# Oscar_s_second_Schematic.net
KiCad netlist of a schematic drawn in EAGLE
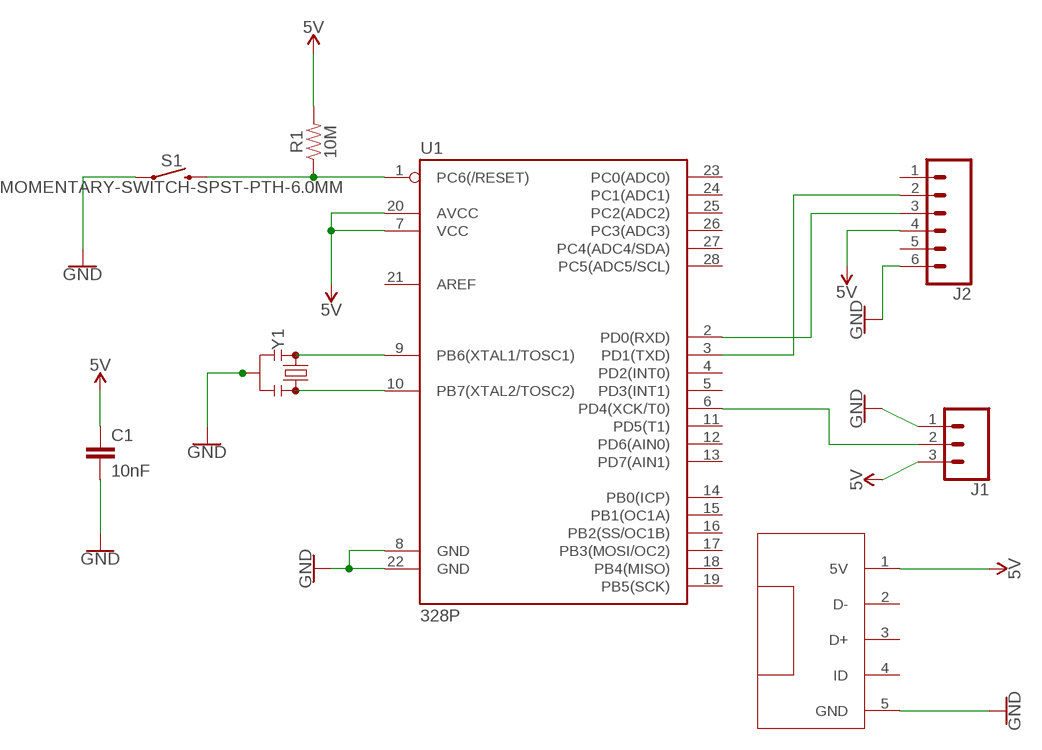
[diagram p0: schematic, sheet 1]

(export (version "E")
  (design (tool "Eeschema 10.0.6"))
  (components
    (comp (ref "C1")
      (value "10nF")
      (footprint "eagle-import:CAP-PTH-10MM")
      (libsource (lib "eagle-import") (part "10NF-PTH-10MM-10000V-1-%"))
    )
    (comp (ref "J1")
      (value "CONN_03")
      (footprint "eagle-import:1X03")
      (libsource (lib "eagle-import") (part "CONN_03"))
    )
    (comp (ref "J2")
      (value "CONN_06SILK_FEMALE_PTH")
      (footprint "eagle-import:1X06")
      (libsource (lib "eagle-import") (part "CONN_06SILK_FEMALE_PTH"))
    )
    (comp (ref "R1")
      (value "10M")
      (footprint "eagle-import:AXIAL-0.3")
      (libsource (lib "eagle-import") (part "10MOHM-HORIZ-1/4W-5%"))
    )
    (comp (ref "S1")
      (value "MOMENTARY-SWITCH-SPST-PTH-6.0MM")
      (footprint "eagle-import:TACTILE_SWITCH_PTH_6.0MM")
      (libsource (lib "eagle-import") (part "MOMENTARY-SWITCH-SPST-PTH-6.0MM"))
    )
    (comp (ref "U$1")
      (value "USB")
      (footprint "eagle-import:USB")
      (libsource (lib "eagle-import") (part "USB"))
    )
    (comp (ref "U1")
      (value "328P")
      (footprint "eagle-import:DIP28")
      (libsource (lib "eagle-import") (part "ATMEGA328P_PDIP"))
    )
    (comp (ref "Y1")
      (value "RESONATORPTH-7.6X3.8")
      (footprint "eagle-import:RESONATOR-PTH-7.6X3.8")
      (libsource (lib "eagle-import") (part "RESONATORPTH-7.6X3.8"))
    )
  )
  (nets
    (net (code "1") (name "5V") (class "Default")
      (node (ref "C1") (pin "1") (pinfunction "1_1") (pintype "passive"))
      (node (ref "J1") (pin "3") (pinfunction "3_3") (pintype "passive"))
      (node (ref "J2") (pin "4") (pinfunction "4_4") (pintype "passive"))
      (node (ref "R1") (pin "P$2") (pinfunction "2_P$2") (pintype "passive"))
      (node (ref "U$1") (pin "1") (pinfunction "5V_1") (pintype "bidirectional"))
      (node (ref "U1") (pin "20") (pinfunction "AVCC_20") (pintype "bidirectional"))
      (node (ref "U1") (pin "7") (pinfunction "VCC_7") (pintype "bidirectional"))
    )
    (net (code "2") (name "GND") (class "Default")
      (node (ref "C1") (pin "2") (pinfunction "2_2") (pintype "passive"))
      (node (ref "J1") (pin "1") (pinfunction "1_1") (pintype "passive"))
      (node (ref "J2") (pin "6") (pinfunction "6_6") (pintype "passive"))
      (node (ref "S1") (pin "1") (pinfunction "1_1") (pintype "passive"))
      (node (ref "U$1") (pin "5") (pinfunction "GND_5") (pintype "bidirectional"))
      (node (ref "U1") (pin "22") (pinfunction "GND_22") (pintype "bidirectional"))
      (node (ref "U1") (pin "8") (pinfunction "GND_8") (pintype "bidirectional"))
      (node (ref "Y1") (pin "2") (pinfunction "2_2") (pintype "passive"))
    )
    (net (code "3") (name "Net-(R1-1)") (class "Default")
      (node (ref "R1") (pin "P$1") (pinfunction "1_P$1") (pintype "passive"))
      (node (ref "S1") (pin "3") (pinfunction "2_3") (pintype "passive"))
      (node (ref "U1") (pin "1") (pinfunction "PC6(/RESET)_1") (pintype "bidirectional"))
    )
    (net (code "4") (name "Net-(U1-PB6(XTAL1{slash}TOSC1))") (class "Default")
      (node (ref "U1") (pin "9") (pinfunction "PB6(XTAL1/TOSC1)_9") (pintype "bidirectional"))
      (node (ref "Y1") (pin "1") (pinfunction "1_1") (pintype "passive"))
    )
    (net (code "5") (name "Net-(U1-PB7(XTAL2{slash}TOSC2))") (class "Default")
      (node (ref "U1") (pin "10") (pinfunction "PB7(XTAL2/TOSC2)_10") (pintype "bidirectional"))
      (node (ref "Y1") (pin "3") (pinfunction "3_3") (pintype "passive"))
    )
    (net (code "6") (name "Net-(U1-PD0(RXD))") (class "Default")
      (node (ref "J2") (pin "3") (pinfunction "3_3") (pintype "passive"))
      (node (ref "U1") (pin "2") (pinfunction "PD0(RXD)_2") (pintype "bidirectional"))
    )
    (net (code "7") (name "Net-(U1-PD1(TXD))") (class "Default")
      (node (ref "J2") (pin "2") (pinfunction "2_2") (pintype "passive"))
      (node (ref "U1") (pin "3") (pinfunction "PD1(TXD)_3") (pintype "bidirectional"))
    )
    (net (code "8") (name "Net-(U1-PD4(XCK{slash}T0))") (class "Default")
      (node (ref "J1") (pin "2") (pinfunction "2_2") (pintype "passive"))
      (node (ref "U1") (pin "6") (pinfunction "PD4(XCK/T0)_6") (pintype "bidirectional"))
    )
    (net (code "9") (name "unconnected-(J2-Pad1)") (class "Default")
      (node (ref "J2") (pin "1") (pinfunction "1_1") (pintype "passive"))
    )
    (net (code "10") (name "unconnected-(J2-Pad5)") (class "Default")
      (node (ref "J2") (pin "5") (pinfunction "5_5") (pintype "passive"))
    )
    (net (code "11") (name "unconnected-(U$1-D+-Pad3)") (class "Default")
      (node (ref "U$1") (pin "3") (pinfunction "D+_3") (pintype "bidirectional"))
    )
    (net (code "12") (name "unconnected-(U$1-D--Pad2)") (class "Default")
      (node (ref "U$1") (pin "2") (pinfunction "D-_2") (pintype "bidirectional"))
    )
    (net (code "13") (name "unconnected-(U$1-ID-Pad4)") (class "Default")
      (node (ref "U$1") (pin "4") (pinfunction "ID_4") (pintype "bidirectional"))
    )
    (net (code "14") (name "unconnected-(U1-AREF-Pad21)") (class "Default")
      (node (ref "U1") (pin "21") (pinfunction "AREF_21") (pintype "bidirectional"))
    )
    (net (code "15") (name "unconnected-(U1-PB0(ICP)-Pad14)") (class "Default")
      (node (ref "U1") (pin "14") (pinfunction "PB0(ICP)_14") (pintype "bidirectional"))
    )
    (net (code "16") (name "unconnected-(U1-PB1(OC1A)-Pad15)") (class "Default")
      (node (ref "U1") (pin "15") (pinfunction "PB1(OC1A)_15") (pintype "bidirectional"))
    )
    (net (code "17") (name "unconnected-(U1-PB2(SS{slash}OC1B)-Pad16)") (class "Default")
      (node (ref "U1") (pin "16") (pinfunction "PB2(SS/OC1B)_16") (pintype "bidirectional"))
    )
    (net (code "18") (name "unconnected-(U1-PB3(MOSI{slash}OC2)-Pad17)") (class "Default")
      (node (ref "U1") (pin "17") (pinfunction "PB3(MOSI/OC2)_17") (pintype "bidirectional"))
    )
    (net (code "19") (name "unconnected-(U1-PB4(MISO)-Pad18)") (class "Default")
      (node (ref "U1") (pin "18") (pinfunction "PB4(MISO)_18") (pintype "bidirectional"))
    )
    (net (code "20") (name "unconnected-(U1-PB5(SCK)-Pad19)") (class "Default")
      (node (ref "U1") (pin "19") (pinfunction "PB5(SCK)_19") (pintype "bidirectional"))
    )
    (net (code "21") (name "unconnected-(U1-PC0(ADC0)-Pad23)") (class "Default")
      (node (ref "U1") (pin "23") (pinfunction "PC0(ADC0)_23") (pintype "bidirectional"))
    )
    (net (code "22") (name "unconnected-(U1-PC1(ADC1)-Pad24)") (class "Default")
      (node (ref "U1") (pin "24") (pinfunction "PC1(ADC1)_24") (pintype "bidirectional"))
    )
    (net (code "23") (name "unconnected-(U1-PC2(ADC2)-Pad25)") (class "Default")
      (node (ref "U1") (pin "25") (pinfunction "PC2(ADC2)_25") (pintype "bidirectional"))
    )
    (net (code "24") (name "unconnected-(U1-PC3(ADC3)-Pad26)") (class "Default")
      (node (ref "U1") (pin "26") (pinfunction "PC3(ADC3)_26") (pintype "bidirectional"))
    )
    (net (code "25") (name "unconnected-(U1-PC4(ADC4{slash}SDA)-Pad27)") (class "Default")
      (node (ref "U1") (pin "27") (pinfunction "PC4(ADC4/SDA)_27") (pintype "bidirectional"))
    )
    (net (code "26") (name "unconnected-(U1-PC5(ADC5{slash}SCL)-Pad28)") (class "Default")
      (node (ref "U1") (pin "28") (pinfunction "PC5(ADC5/SCL)_28") (pintype "bidirectional"))
    )
    (net (code "27") (name "unconnected-(U1-PD2(INT0)-Pad4)") (class "Default")
      (node (ref "U1") (pin "4") (pinfunction "PD2(INT0)_4") (pintype "bidirectional"))
    )
    (net (code "28") (name "unconnected-(U1-PD3(INT1)-Pad5)") (class "Default")
      (node (ref "U1") (pin "5") (pinfunction "PD3(INT1)_5") (pintype "bidirectional"))
    )
    (net (code "29") (name "unconnected-(U1-PD5(T1)-Pad11)") (class "Default")
      (node (ref "U1") (pin "11") (pinfunction "PD5(T1)_11") (pintype "bidirectional"))
    )
    (net (code "30") (name "unconnected-(U1-PD6(AIN0)-Pad12)") (class "Default")
      (node (ref "U1") (pin "12") (pinfunction "PD6(AIN0)_12") (pintype "bidirectional"))
    )
    (net (code "31") (name "unconnected-(U1-PD7(AIN1)-Pad13)") (class "Default")
      (node (ref "U1") (pin "13") (pinfunction "PD7(AIN1)_13") (pintype "bidirectional"))
    )
  )
)
